# Esquematico.net
KiCad netlist of a schematic drawn in Altium Designer
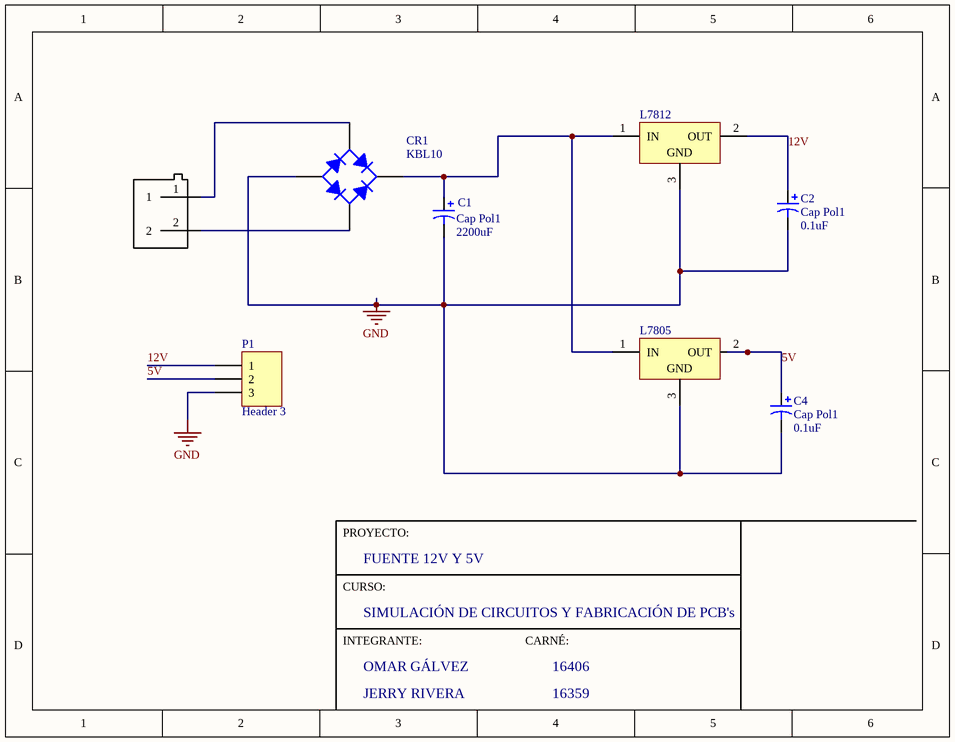
[diagram p0: Esquematico.SchDoc]

(export (version "E")
  (design (tool "Eeschema 10.0.6"))
  (components
    (comp (ref "C1")
      (value "Cap Pol1")
      (footprint "CAP220:CAPPRD500W60D1250HXXX-V")
      (description "Polarized Capacitor (Radial)")
      (fields (field (name "ALTIUM_VALUE") "2200uF") (field (name "PUBLISHER") "Altium Limited"))
      (libsource (lib "Miscellaneous Devices") (part "Cap Pol1"))
    )
    (comp (ref "C2")
      (value "Cap Pol1")
      (footprint "CAP0_1:CAPPRD200W50D500HXXX-V")
      (description "Polarized Capacitor (Radial)")
      (fields (field (name "ALTIUM_VALUE") "0.1uF") (field (name "PUBLISHER") "Altium Limited"))
      (libsource (lib "Miscellaneous Devices") (part "Cap Pol1"))
    )
    (comp (ref "C4")
      (value "Cap Pol1")
      (footprint "CAP0_1:CAPPRD200W50D500HXXX-V")
      (description "Polarized Capacitor (Radial)")
      (fields (field (name "ALTIUM_VALUE") "0.1uF") (field (name "PUBLISHER") "Altium Limited"))
      (libsource (lib "Miscellaneous Devices") (part "Cap Pol1"))
    )
    (comp (ref "CR1")
      (value "KBL10")
      (footprint "IR Rectifier - Bridge:D-37")
      (description "4 Amp Rectifier Bridge")
      (fields (field (name "PUBLISHER") "Altium Limited"))
      (libsource (lib "IR Rectifier - Bridge") (part "KBL10"))
    )
    (comp (ref "L7805")
      (value "L7805ACV")
      (footprint "ST Power Mgt Voltage Regulator:TO220ABN")
      (description "Precision 1A Regulator")
      (fields (field (name "PUBLISHER") "Altium Limited"))
      (libsource (lib "ST Power Mgt Voltage Regulator") (part "L7805ACV"))
    )
    (comp (ref "L7812")
      (value "L7812ACV")
      (footprint "ST Power Mgt Voltage Regulator:TO220ABN")
      (description "Precision 1A Regulator")
      (fields (field (name "PUBLISHER") "Altium Limited"))
      (libsource (lib "ST Power Mgt Voltage Regulator") (part "L7812ACV"))
    )
    (comp (ref "P1")
      (value "Header 3")
      (footprint "Miscellaneous Connectors:HDR1X3")
      (description "Header, 3-Pin")
      (fields (field (name "PUBLISHER") "Altium Limited"))
      (libsource (lib "Miscellaneous Connectors") (part "Header 3"))
    )
    (comp (ref "TerminalBlock1")
      (value "Terminales")
      (footprint "TerminalBlock")
      (libsource (lib "2pines") (part "TerminalBlock?"))
    )
  )
  (nets
    (net (code "1") (name "/5V") (class "Default")
      (node (ref "C4") (pin "1") (pinfunction "1_1") (pintype "passive"))
      (node (ref "L7805") (pin "2") (pinfunction "OUT_2") (pintype "power_in"))
      (node (ref "P1") (pin "2") (pinfunction "2_2") (pintype "passive"))
    )
    (net (code "2") (name "/12V") (class "Default")
      (node (ref "C2") (pin "1") (pinfunction "1_1") (pintype "passive"))
      (node (ref "L7812") (pin "2") (pinfunction "OUT_2") (pintype "power_in"))
      (node (ref "P1") (pin "1") (pinfunction "1_1") (pintype "passive"))
    )
    (net (code "3") (name "GND") (class "Default")
      (node (ref "C1") (pin "2") (pinfunction "2_2") (pintype "passive"))
      (node (ref "C2") (pin "2") (pinfunction "2_2") (pintype "passive"))
      (node (ref "C4") (pin "2") (pinfunction "2_2") (pintype "passive"))
      (node (ref "CR1") (pin "3") (pinfunction "A_3") (pintype "passive"))
      (node (ref "L7805") (pin "3") (pinfunction "GND_3") (pintype "power_in"))
      (node (ref "L7812") (pin "3") (pinfunction "GND_3") (pintype "power_in"))
      (node (ref "P1") (pin "3") (pinfunction "3_3") (pintype "passive"))
    )
    (net (code "4") (name "Net-(CR1-C-Pad2)") (class "Default")
      (node (ref "CR1") (pin "2") (pinfunction "C_2") (pintype "passive"))
      (node (ref "TerminalBlock1") (pin "2") (pinfunction "2_2") (pintype "passive"))
    )
    (net (code "5") (name "Net-(CR1-C-Pad4)") (class "Default")
      (node (ref "CR1") (pin "4") (pinfunction "C_4") (pintype "passive"))
      (node (ref "TerminalBlock1") (pin "1") (pinfunction "1_1") (pintype "passive"))
    )
    (net (code "6") (name "Net-(CR1-K)") (class "Default")
      (node (ref "C1") (pin "1") (pinfunction "1_1") (pintype "passive"))
      (node (ref "CR1") (pin "1") (pinfunction "K_1") (pintype "passive"))
      (node (ref "L7805") (pin "1") (pinfunction "IN_1") (pintype "power_in"))
      (node (ref "L7812") (pin "1") (pinfunction "IN_1") (pintype "power_in"))
    )
  )
)
